# cc2650_48.net
KiCad netlist of a schematic drawn in EAGLE
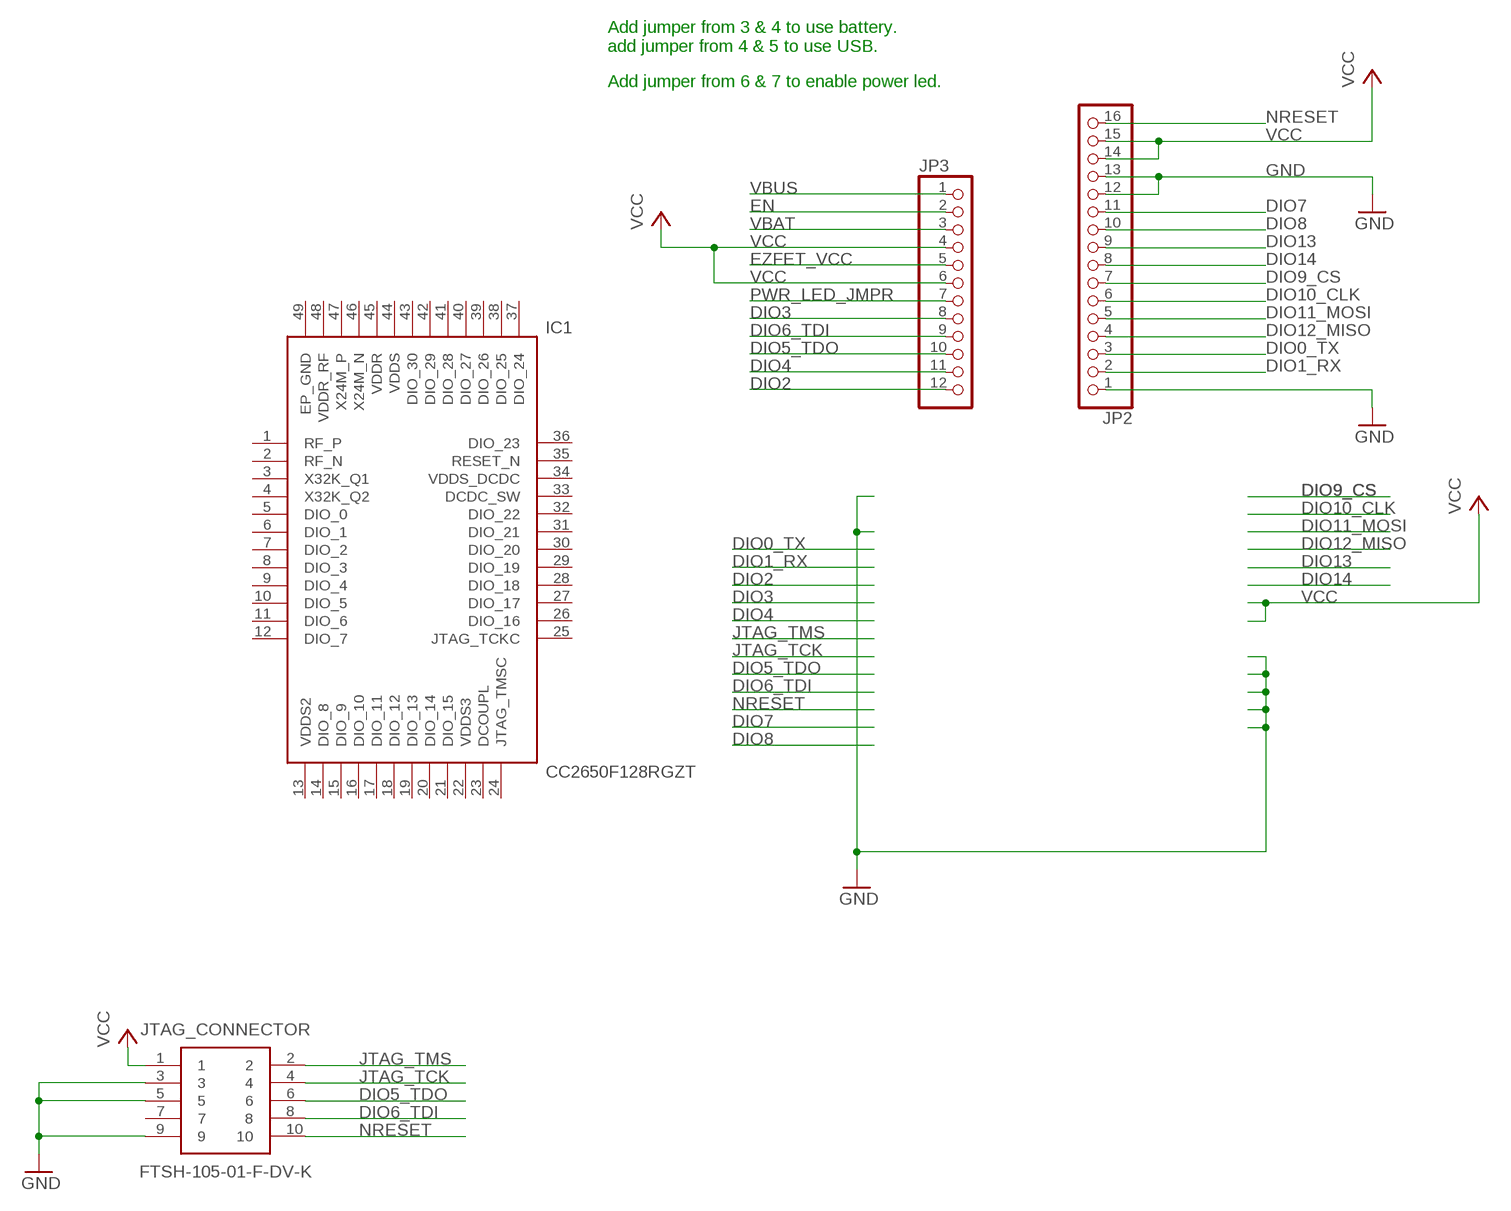
[diagram p0: schematic, sheet 1, part 1 of 2]
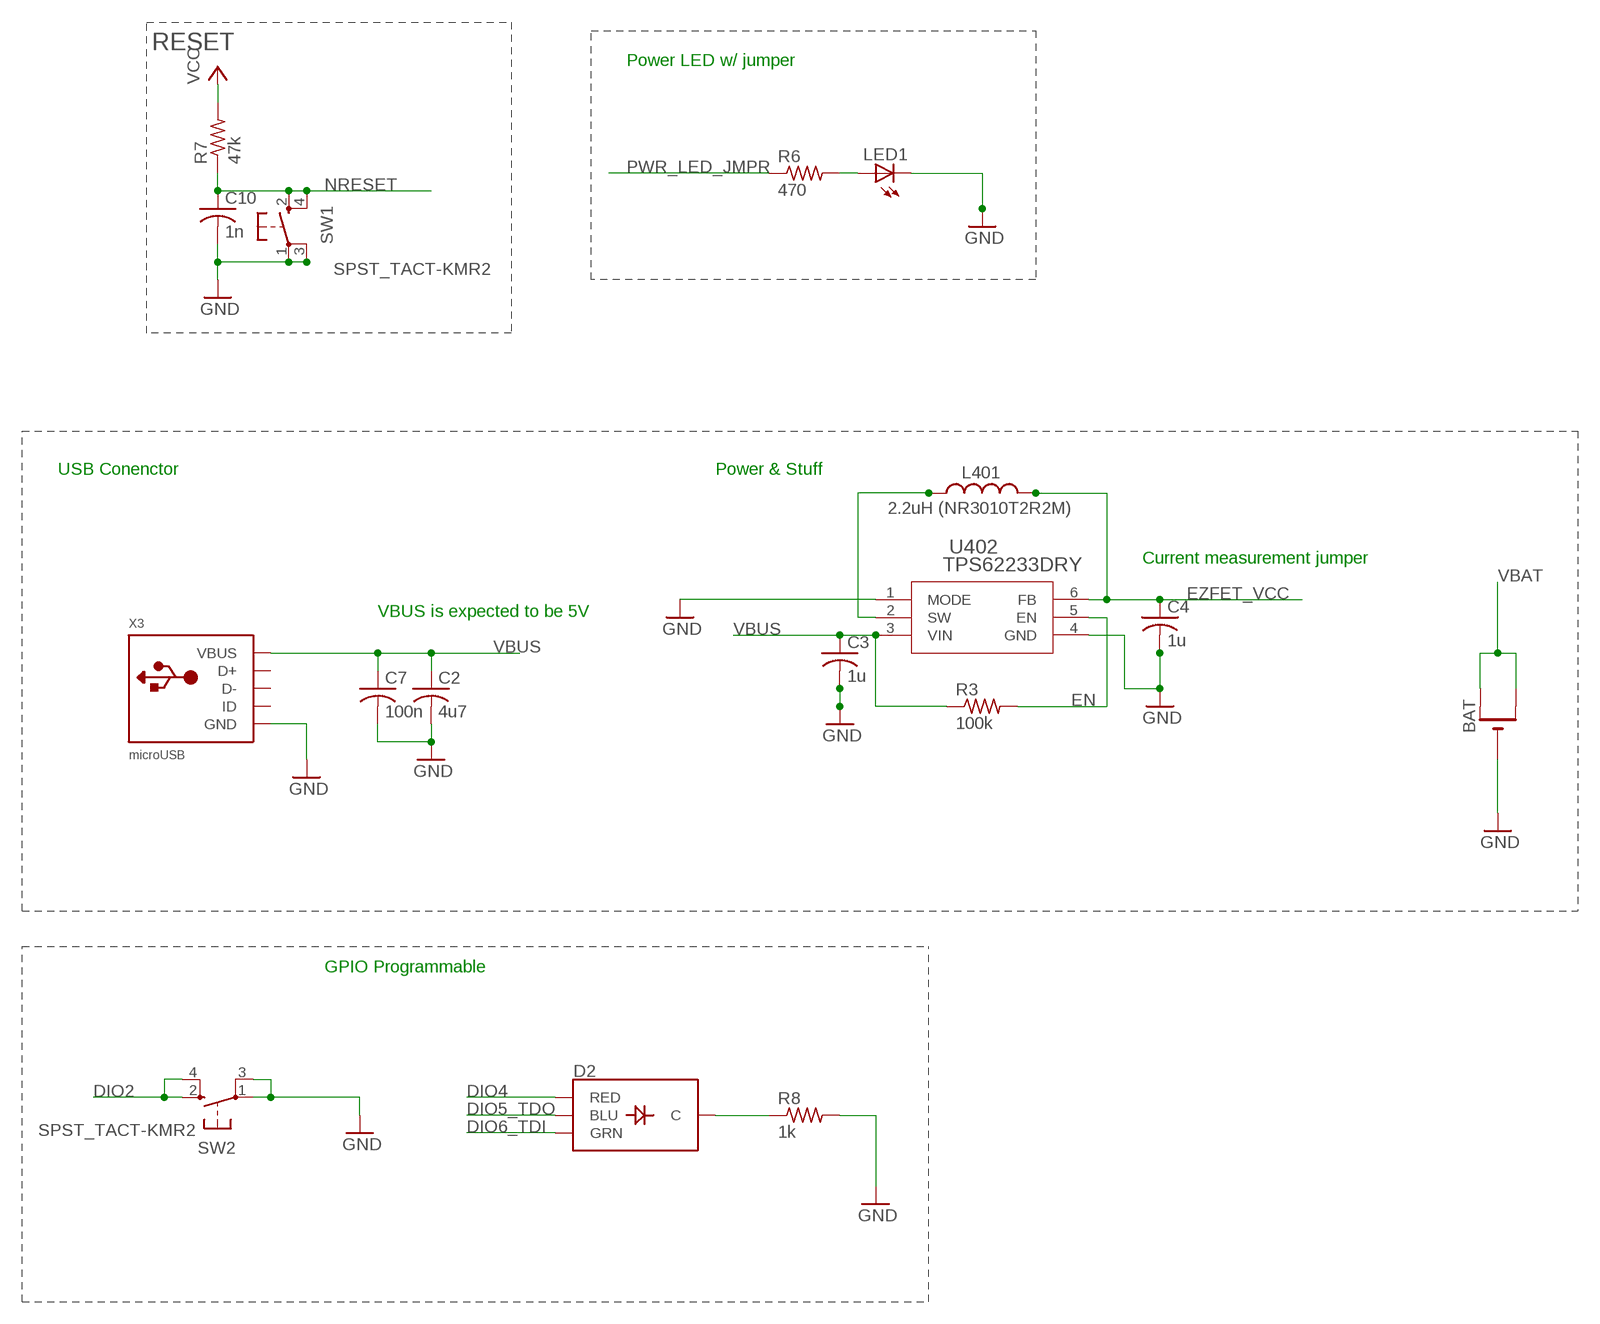
[diagram p1: schematic, sheet 1, part 2 of 2]

(export (version "E")
  (design (tool "Eeschema 10.0.6"))
  (components
    (comp (ref "BAT")
      (value "CR1220THM")
      (footprint "eagle-import:CR1220-THM")
      (fields (field (name "MF") "KEYSTONE ELECTR") (field (name "MPN") "3000"))
      (libsource (lib "eagle-import") (part "CR1220THM"))
    )
    (comp (ref "C2")
      (value "4u7")
      (footprint "eagle-import:C1206")
      (fields (field (name "MPN") "GRT31CC81E475KE01L"))
      (libsource (lib "eagle-import") (part "C-USC1206"))
    )
    (comp (ref "C3")
      (value "1u")
      (footprint "eagle-import:C0805")
      (fields (field (name "MPN") "C0805C105K5RACTU"))
      (libsource (lib "eagle-import") (part "C-USC0805"))
    )
    (comp (ref "C4")
      (value "1u")
      (footprint "eagle-import:C0805")
      (fields (field (name "MPN") "C0805C105K5RACTU"))
      (libsource (lib "eagle-import") (part "C-USC0805"))
    )
    (comp (ref "C7")
      (value "100n")
      (footprint "eagle-import:C0805")
      (libsource (lib "eagle-import") (part "C-USC0805"))
    )
    (comp (ref "C10")
      (value "1n")
      (footprint "eagle-import:C0805")
      (libsource (lib "eagle-import") (part "C-USC0805"))
    )
    (comp (ref "D2")
      (value "LED-RGB-CCPIRANHA")
      (footprint "eagle-import:LED_PIRANHA_5MM")
      (fields (field (name "MPN") "CLMVB-FKA-CFHEHLCBB7A363"))
      (libsource (lib "eagle-import") (part "LED-RGB-CCPIRANHA"))
    )
    (comp (ref "IC1")
      (value "CC2650F128RGZT")
      (footprint "eagle-import:QFN50P700X700X100-49N")
      (fields (field (name "RS_PART_NUMBER") "8751012P"))
      (libsource (lib "eagle-import") (part "CC2650F128RGZT"))
    )
    (comp (ref "JP2")
      (value "HEADER-1X16ROUND")
      (footprint "eagle-import:1X16_ROUND")
      (libsource (lib "eagle-import") (part "HEADER-1X16ROUND"))
    )
    (comp (ref "JP3")
      (value "HEADER-1X12")
      (footprint "eagle-import:1X12_ROUND")
      (libsource (lib "eagle-import") (part "HEADER-1X12"))
    )
    (comp (ref "JTAG_CONNECTOR")
      (value "FTSH-105-01-F-DV-K")
      (footprint "eagle-import:SAMTEC_FTSH-105-01-L-DV")
      (libsource (lib "eagle-import") (part "FTSH-105-01-F-DV-K"))
    )
    (comp (ref "L401")
      (value "2.2uH (NR3010T2R2M)")
      (footprint "eagle-import:L-NR3010")
      (fields (field (name "MPN") "NR3010T2R2M"))
      (libsource (lib "eagle-import") (part "L-NR3010"))
    )
    (comp (ref "LED1")
      (value "LEDCHIPLED_0805")
      (footprint "eagle-import:CHIPLED_0805")
      (libsource (lib "eagle-import") (part "LEDCHIPLED_0805"))
    )
    (comp (ref "R3")
      (value "100k")
      (footprint "eagle-import:R0805")
      (libsource (lib "eagle-import") (part "R-US_R0805"))
    )
    (comp (ref "R6")
      (value "470")
      (footprint "eagle-import:R0805")
      (libsource (lib "eagle-import") (part "R-US_R0805"))
    )
    (comp (ref "R7")
      (value "47k")
      (footprint "eagle-import:R0805")
      (libsource (lib "eagle-import") (part "R-US_R0805"))
    )
    (comp (ref "R8")
      (value "1k")
      (footprint "eagle-import:R0805")
      (libsource (lib "eagle-import") (part "R-US_R0805"))
    )
    (comp (ref "SW1")
      (value "SPST_TACT-KMR2")
      (footprint "eagle-import:KMR2")
      (libsource (lib "eagle-import") (part "SPST_TACT-KMR2"))
    )
    (comp (ref "SW2")
      (value "SPST_TACT-KMR2")
      (footprint "eagle-import:KMR2")
      (libsource (lib "eagle-import") (part "SPST_TACT-KMR2"))
    )
    (comp (ref "U402")
      (value "TPS62233DRY")
      (footprint "eagle-import:DRY6")
      (fields
        (field (name "GENERIC_PART_NUMBER") "TPS62231")
        (field (name "MANUFACTURER") "Texas Instruments")
        (field (name "MANUFACTURER_PART_NUMBER") "tps62231_dry_6")
      )
      (libsource (lib "eagle-import") (part "TPS6223X_DRY_6"))
    )
    (comp (ref "X3")
      (value "microUSB")
      (footprint "eagle-import:4UCONN_20329_V2")
      (libsource (lib "eagle-import") (part "USB_MICRO_20329_V2"))
    )
  )
  (nets
    (net (code "1") (name "/DIO0_TX") (class "Default")
      (node (ref "JP2") (pin "3") (pinfunction "3_3") (pintype "passive"))
    )
    (net (code "2") (name "/DIO1_RX") (class "Default")
      (node (ref "JP2") (pin "2") (pinfunction "2_2") (pintype "passive"))
    )
    (net (code "3") (name "/DIO2") (class "Default")
      (node (ref "JP3") (pin "12") (pinfunction "12_12") (pintype "passive"))
      (node (ref "SW2") (pin "2") (pinfunction "S_2") (pintype "passive"))
      (node (ref "SW2") (pin "4") (pinfunction "S1_4") (pintype "passive"))
    )
    (net (code "4") (name "/DIO3") (class "Default")
      (node (ref "JP3") (pin "8") (pinfunction "8_8") (pintype "passive"))
    )
    (net (code "5") (name "/DIO4") (class "Default")
      (node (ref "D2") (pin "R") (pinfunction "RED_R") (pintype "bidirectional"))
      (node (ref "JP3") (pin "11") (pinfunction "11_11") (pintype "passive"))
    )
    (net (code "6") (name "/DIO5_TDO") (class "Default")
      (node (ref "D2") (pin "B") (pinfunction "BLU_B") (pintype "bidirectional"))
      (node (ref "JP3") (pin "10") (pinfunction "10_10") (pintype "passive"))
      (node (ref "JTAG_CONNECTOR") (pin "6") (pinfunction "6_6") (pintype "passive"))
    )
    (net (code "7") (name "/DIO6_TDI") (class "Default")
      (node (ref "D2") (pin "G") (pinfunction "GRN_G") (pintype "bidirectional"))
      (node (ref "JP3") (pin "9") (pinfunction "9_9") (pintype "passive"))
      (node (ref "JTAG_CONNECTOR") (pin "8") (pinfunction "8_8") (pintype "passive"))
    )
    (net (code "8") (name "/DIO7") (class "Default")
      (node (ref "JP2") (pin "11") (pinfunction "11_11") (pintype "passive"))
    )
    (net (code "9") (name "/DIO8") (class "Default")
      (node (ref "JP2") (pin "10") (pinfunction "10_10") (pintype "passive"))
    )
    (net (code "10") (name "/DIO9_CS") (class "Default")
      (node (ref "JP2") (pin "7") (pinfunction "7_7") (pintype "passive"))
    )
    (net (code "11") (name "/DIO10_CLK") (class "Default")
      (node (ref "JP2") (pin "6") (pinfunction "6_6") (pintype "passive"))
    )
    (net (code "12") (name "/DIO11_MOSI") (class "Default")
      (node (ref "JP2") (pin "5") (pinfunction "5_5") (pintype "passive"))
    )
    (net (code "13") (name "/DIO12_MISO") (class "Default")
      (node (ref "JP2") (pin "4") (pinfunction "4_4") (pintype "passive"))
    )
    (net (code "14") (name "/DIO13") (class "Default")
      (node (ref "JP2") (pin "9") (pinfunction "9_9") (pintype "passive"))
    )
    (net (code "15") (name "/DIO14") (class "Default")
      (node (ref "JP2") (pin "8") (pinfunction "8_8") (pintype "passive"))
    )
    (net (code "16") (name "/EN") (class "Default")
      (node (ref "JP3") (pin "2") (pinfunction "2_2") (pintype "passive"))
      (node (ref "R3") (pin "2") (pinfunction "2_2") (pintype "passive"))
      (node (ref "U402") (pin "5") (pinfunction "EN_5") (pintype "input"))
    )
    (net (code "17") (name "/EP_GND") (class "Default")
      (node (ref "IC1") (pin "49") (pinfunction "EP_GND_49") (pintype "power_in"))
    )
    (net (code "18") (name "/EZFET_VCC") (class "Default")
      (node (ref "C4") (pin "1") (pinfunction "1_1") (pintype "passive"))
      (node (ref "JP3") (pin "5") (pinfunction "5_5") (pintype "passive"))
      (node (ref "L401") (pin "P$2") (pinfunction "2_P$2") (pintype "passive"))
      (node (ref "U402") (pin "6") (pinfunction "FB_6") (pintype "input"))
    )
    (net (code "19") (name "/JTAG_TCK") (class "Default")
      (node (ref "JTAG_CONNECTOR") (pin "4") (pinfunction "4_4") (pintype "passive"))
    )
    (net (code "20") (name "/JTAG_TMS") (class "Default")
      (node (ref "JTAG_CONNECTOR") (pin "2") (pinfunction "2_2") (pintype "passive"))
    )
    (net (code "21") (name "/NRESET") (class "Default")
      (node (ref "C10") (pin "1") (pinfunction "1_1") (pintype "passive"))
      (node (ref "JP2") (pin "16") (pinfunction "16_16") (pintype "passive"))
      (node (ref "JTAG_CONNECTOR") (pin "10") (pinfunction "10_10") (pintype "passive"))
      (node (ref "R7") (pin "1") (pinfunction "1_1") (pintype "passive"))
      (node (ref "SW1") (pin "2") (pinfunction "S_2") (pintype "passive"))
      (node (ref "SW1") (pin "4") (pinfunction "S1_4") (pintype "passive"))
    )
    (net (code "22") (name "/PWR_LED_JMPR") (class "Default")
      (node (ref "JP3") (pin "7") (pinfunction "7_7") (pintype "passive"))
      (node (ref "R6") (pin "1") (pinfunction "1_1") (pintype "passive"))
    )
    (net (code "23") (name "/VBAT") (class "Default")
      (node (ref "BAT") (pin "+1") (pinfunction "+_+1") (pintype "passive"))
      (node (ref "BAT") (pin "+2") (pinfunction "+1_+2") (pintype "passive"))
      (node (ref "JP3") (pin "3") (pinfunction "3_3") (pintype "passive"))
    )
    (net (code "24") (name "/VBUS") (class "Default")
      (node (ref "C2") (pin "1") (pinfunction "1_1") (pintype "passive"))
      (node (ref "C3") (pin "1") (pinfunction "1_1") (pintype "passive"))
      (node (ref "C7") (pin "1") (pinfunction "1_1") (pintype "passive"))
      (node (ref "JP3") (pin "1") (pinfunction "1_1") (pintype "passive"))
      (node (ref "R3") (pin "1") (pinfunction "1_1") (pintype "passive"))
      (node (ref "U402") (pin "3") (pinfunction "VIN_3") (pintype "power_in"))
      (node (ref "X3") (pin "VBUS") (pinfunction "VBUS_VBUS") (pintype "power_in"))
    )
    (net (code "25") (name "/VDDR") (class "Default")
      (node (ref "IC1") (pin "45") (pinfunction "VDDR_45") (pintype "power_in"))
    )
    (net (code "26") (name "/VDDR_RF") (class "Default")
      (node (ref "IC1") (pin "48") (pinfunction "VDDR_RF_48") (pintype "power_in"))
    )
    (net (code "27") (name "/VDDS") (class "Default")
      (node (ref "IC1") (pin "44") (pinfunction "VDDS_44") (pintype "power_in"))
    )
    (net (code "28") (name "/VDDS2") (class "Default")
      (node (ref "IC1") (pin "13") (pinfunction "VDDS2_13") (pintype "power_in"))
    )
    (net (code "29") (name "/VDDS3") (class "Default")
      (node (ref "IC1") (pin "22") (pinfunction "VDDS3_22") (pintype "power_in"))
    )
    (net (code "30") (name "/VDDS_DCDC") (class "Default")
      (node (ref "IC1") (pin "34") (pinfunction "VDDS_DCDC_34") (pintype "power_in"))
    )
    (net (code "31") (name "GND") (class "Default")
      (node (ref "BAT") (pin "-") (pinfunction "-_-") (pintype "passive"))
      (node (ref "C10") (pin "2") (pinfunction "2_2") (pintype "passive"))
      (node (ref "C2") (pin "2") (pinfunction "2_2") (pintype "passive"))
      (node (ref "C3") (pin "2") (pinfunction "2_2") (pintype "passive"))
      (node (ref "C4") (pin "2") (pinfunction "2_2") (pintype "passive"))
      (node (ref "C7") (pin "2") (pinfunction "2_2") (pintype "passive"))
      (node (ref "JP2") (pin "1") (pinfunction "1_1") (pintype "passive"))
      (node (ref "JP2") (pin "12") (pinfunction "12_12") (pintype "passive"))
      (node (ref "JP2") (pin "13") (pinfunction "13_13") (pintype "passive"))
      (node (ref "JTAG_CONNECTOR") (pin "3") (pinfunction "3_3") (pintype "passive"))
      (node (ref "JTAG_CONNECTOR") (pin "5") (pinfunction "5_5") (pintype "passive"))
      (node (ref "JTAG_CONNECTOR") (pin "9") (pinfunction "9_9") (pintype "passive"))
      (node (ref "LED1") (pin "C") (pinfunction "C_C") (pintype "passive"))
      (node (ref "R8") (pin "2") (pinfunction "2_2") (pintype "passive"))
      (node (ref "SW1") (pin "1") (pinfunction "P_1") (pintype "passive"))
      (node (ref "SW1") (pin "3") (pinfunction "P1_3") (pintype "passive"))
      (node (ref "SW2") (pin "1") (pinfunction "P_1") (pintype "passive"))
      (node (ref "SW2") (pin "3") (pinfunction "P1_3") (pintype "passive"))
      (node (ref "U402") (pin "1") (pinfunction "MODE_1") (pintype "input"))
      (node (ref "U402") (pin "4") (pinfunction "GND_4") (pintype "power_in"))
      (node (ref "X3") (pin "BASE@1") (pinfunction "GND_BASE@1") (pintype "power_in"))
      (node (ref "X3") (pin "BASE@2") (pinfunction "GND_BASE@2") (pintype "power_in"))
      (node (ref "X3") (pin "GND") (pinfunction "GND_GND") (pintype "power_in"))
      (node (ref "X3") (pin "SPRT@1") (pinfunction "GND_SPRT@1") (pintype "power_in"))
      (node (ref "X3") (pin "SPRT@2") (pinfunction "GND_SPRT@2") (pintype "power_in"))
      (node (ref "X3") (pin "SPRT@3") (pinfunction "GND_SPRT@3") (pintype "power_in"))
      (node (ref "X3") (pin "SPRT@4") (pinfunction "GND_SPRT@4") (pintype "power_in"))
    )
    (net (code "32") (name "Net-(D2-C)") (class "Default")
      (node (ref "D2") (pin "-") (pinfunction "C_-") (pintype "bidirectional"))
      (node (ref "R8") (pin "1") (pinfunction "1_1") (pintype "passive"))
    )
    (net (code "33") (name "Net-(L401-1)") (class "Default")
      (node (ref "L401") (pin "P$1") (pinfunction "1_P$1") (pintype "passive"))
      (node (ref "U402") (pin "2") (pinfunction "SW_2") (pintype "output"))
    )
    (net (code "34") (name "Net-(LED1-PadA)") (class "Default")
      (node (ref "LED1") (pin "A") (pinfunction "A_A") (pintype "passive"))
      (node (ref "R6") (pin "2") (pinfunction "2_2") (pintype "passive"))
    )
    (net (code "35") (name "VCC") (class "Default")
      (node (ref "JP2") (pin "14") (pinfunction "14_14") (pintype "passive"))
      (node (ref "JP2") (pin "15") (pinfunction "15_15") (pintype "passive"))
      (node (ref "JP3") (pin "4") (pinfunction "4_4") (pintype "passive"))
      (node (ref "JP3") (pin "6") (pinfunction "6_6") (pintype "passive"))
      (node (ref "JTAG_CONNECTOR") (pin "1") (pinfunction "1_1") (pintype "passive"))
      (node (ref "R7") (pin "2") (pinfunction "2_2") (pintype "passive"))
    )
    (net (code "36") (name "unconnected-(IC1-DCDC_SW-Pad33)") (class "Default")
      (node (ref "IC1") (pin "33") (pinfunction "DCDC_SW_33") (pintype "passive"))
    )
    (net (code "37") (name "unconnected-(IC1-DCOUPL-Pad23)") (class "Default")
      (node (ref "IC1") (pin "23") (pinfunction "DCOUPL_23") (pintype "passive"))
    )
    (net (code "38") (name "unconnected-(IC1-DIO_0-Pad5)") (class "Default")
      (node (ref "IC1") (pin "5") (pinfunction "DIO_0_5") (pintype "bidirectional"))
    )
    (net (code "39") (name "unconnected-(IC1-DIO_1-Pad6)") (class "Default")
      (node (ref "IC1") (pin "6") (pinfunction "DIO_1_6") (pintype "bidirectional"))
    )
    (net (code "40") (name "unconnected-(IC1-DIO_2-Pad7)") (class "Default")
      (node (ref "IC1") (pin "7") (pinfunction "DIO_2_7") (pintype "bidirectional"))
    )
    (net (code "41") (name "unconnected-(IC1-DIO_3-Pad8)") (class "Default")
      (node (ref "IC1") (pin "8") (pinfunction "DIO_3_8") (pintype "bidirectional"))
    )
    (net (code "42") (name "unconnected-(IC1-DIO_4-Pad9)") (class "Default")
      (node (ref "IC1") (pin "9") (pinfunction "DIO_4_9") (pintype "bidirectional"))
    )
    (net (code "43") (name "unconnected-(IC1-DIO_5-Pad10)") (class "Default")
      (node (ref "IC1") (pin "10") (pinfunction "DIO_5_10") (pintype "bidirectional"))
    )
    (net (code "44") (name "unconnected-(IC1-DIO_6-Pad11)") (class "Default")
      (node (ref "IC1") (pin "11") (pinfunction "DIO_6_11") (pintype "bidirectional"))
    )
    (net (code "45") (name "unconnected-(IC1-DIO_7-Pad12)") (class "Default")
      (node (ref "IC1") (pin "12") (pinfunction "DIO_7_12") (pintype "bidirectional"))
    )
    (net (code "46") (name "unconnected-(IC1-DIO_8-Pad14)") (class "Default")
      (node (ref "IC1") (pin "14") (pinfunction "DIO_8_14") (pintype "bidirectional"))
    )
    (net (code "47") (name "unconnected-(IC1-DIO_9-Pad15)") (class "Default")
      (node (ref "IC1") (pin "15") (pinfunction "DIO_9_15") (pintype "bidirectional"))
    )
    (net (code "48") (name "unconnected-(IC1-DIO_10-Pad16)") (class "Default")
      (node (ref "IC1") (pin "16") (pinfunction "DIO_10_16") (pintype "bidirectional"))
    )
    (net (code "49") (name "unconnected-(IC1-DIO_11-Pad17)") (class "Default")
      (node (ref "IC1") (pin "17") (pinfunction "DIO_11_17") (pintype "bidirectional"))
    )
    (net (code "50") (name "unconnected-(IC1-DIO_12-Pad18)") (class "Default")
      (node (ref "IC1") (pin "18") (pinfunction "DIO_12_18") (pintype "bidirectional"))
    )
    (net (code "51") (name "unconnected-(IC1-DIO_13-Pad19)") (class "Default")
      (node (ref "IC1") (pin "19") (pinfunction "DIO_13_19") (pintype "bidirectional"))
    )
    (net (code "52") (name "unconnected-(IC1-DIO_14-Pad20)") (class "Default")
      (node (ref "IC1") (pin "20") (pinfunction "DIO_14_20") (pintype "bidirectional"))
    )
    (net (code "53") (name "unconnected-(IC1-DIO_15-Pad21)") (class "Default")
      (node (ref "IC1") (pin "21") (pinfunction "DIO_15_21") (pintype "bidirectional"))
    )
    (net (code "54") (name "unconnected-(IC1-DIO_16-Pad26)") (class "Default")
      (node (ref "IC1") (pin "26") (pinfunction "DIO_16_26") (pintype "bidirectional"))
    )
    (net (code "55") (name "unconnected-(IC1-DIO_17-Pad27)") (class "Default")
      (node (ref "IC1") (pin "27") (pinfunction "DIO_17_27") (pintype "bidirectional"))
    )
    (net (code "56") (name "unconnected-(IC1-DIO_18-Pad28)") (class "Default")
      (node (ref "IC1") (pin "28") (pinfunction "DIO_18_28") (pintype "bidirectional"))
    )
    (net (code "57") (name "unconnected-(IC1-DIO_19-Pad29)") (class "Default")
      (node (ref "IC1") (pin "29") (pinfunction "DIO_19_29") (pintype "bidirectional"))
    )
    (net (code "58") (name "unconnected-(IC1-DIO_20-Pad30)") (class "Default")
      (node (ref "IC1") (pin "30") (pinfunction "DIO_20_30") (pintype "bidirectional"))
    )
    (net (code "59") (name "unconnected-(IC1-DIO_21-Pad31)") (class "Default")
      (node (ref "IC1") (pin "31") (pinfunction "DIO_21_31") (pintype "bidirectional"))
    )
    (net (code "60") (name "unconnected-(IC1-DIO_22-Pad32)") (class "Default")
      (node (ref "IC1") (pin "32") (pinfunction "DIO_22_32") (pintype "bidirectional"))
    )
    (net (code "61") (name "unconnected-(IC1-DIO_23-Pad36)") (class "Default")
      (node (ref "IC1") (pin "36") (pinfunction "DIO_23_36") (pintype "bidirectional"))
    )
    (net (code "62") (name "unconnected-(IC1-DIO_24-Pad37)") (class "Default")
      (node (ref "IC1") (pin "37") (pinfunction "DIO_24_37") (pintype "bidirectional"))
    )
    (net (code "63") (name "unconnected-(IC1-DIO_25-Pad38)") (class "Default")
      (node (ref "IC1") (pin "38") (pinfunction "DIO_25_38") (pintype "bidirectional"))
    )
    (net (code "64") (name "unconnected-(IC1-DIO_26-Pad39)") (class "Default")
      (node (ref "IC1") (pin "39") (pinfunction "DIO_26_39") (pintype "bidirectional"))
    )
    (net (code "65") (name "unconnected-(IC1-DIO_27-Pad40)") (class "Default")
      (node (ref "IC1") (pin "40") (pinfunction "DIO_27_40") (pintype "bidirectional"))
    )
    (net (code "66") (name "unconnected-(IC1-DIO_28-Pad41)") (class "Default")
      (node (ref "IC1") (pin "41") (pinfunction "DIO_28_41") (pintype "bidirectional"))
    )
    (net (code "67") (name "unconnected-(IC1-DIO_29-Pad42)") (class "Default")
      (node (ref "IC1") (pin "42") (pinfunction "DIO_29_42") (pintype "bidirectional"))
    )
    (net (code "68") (name "unconnected-(IC1-DIO_30-Pad43)") (class "Default")
      (node (ref "IC1") (pin "43") (pinfunction "DIO_30_43") (pintype "bidirectional"))
    )
    (net (code "69") (name "unconnected-(IC1-JTAG_TCKC-Pad25)") (class "Default")
      (node (ref "IC1") (pin "25") (pinfunction "JTAG_TCKC_25") (pintype "passive"))
    )
    (net (code "70") (name "unconnected-(IC1-JTAG_TMSC-Pad24)") (class "Default")
      (node (ref "IC1") (pin "24") (pinfunction "JTAG_TMSC_24") (pintype "passive"))
    )
    (net (code "71") (name "unconnected-(IC1-RESET_N-Pad35)") (class "Default")
      (node (ref "IC1") (pin "35") (pinfunction "RESET_N_35") (pintype "passive"))
    )
    (net (code "72") (name "unconnected-(IC1-RF_N-Pad2)") (class "Default")
      (node (ref "IC1") (pin "2") (pinfunction "RF_N_2") (pintype "passive"))
    )
    (net (code "73") (name "unconnected-(IC1-RF_P-Pad1)") (class "Default")
      (node (ref "IC1") (pin "1") (pinfunction "RF_P_1") (pintype "passive"))
    )
    (net (code "74") (name "unconnected-(IC1-X24M_N-Pad46)") (class "Default")
      (node (ref "IC1") (pin "46") (pinfunction "X24M_N_46") (pintype "passive"))
    )
    (net (code "75") (name "unconnected-(IC1-X24M_P-Pad47)") (class "Default")
      (node (ref "IC1") (pin "47") (pinfunction "X24M_P_47") (pintype "passive"))
    )
    (net (code "76") (name "unconnected-(IC1-X32K_Q1-Pad3)") (class "Default")
      (node (ref "IC1") (pin "3") (pinfunction "X32K_Q1_3") (pintype "passive"))
    )
    (net (code "77") (name "unconnected-(IC1-X32K_Q2-Pad4)") (class "Default")
      (node (ref "IC1") (pin "4") (pinfunction "X32K_Q2_4") (pintype "passive"))
    )
    (net (code "78") (name "unconnected-(JTAG_CONNECTOR-Pad7)") (class "Default")
      (node (ref "JTAG_CONNECTOR") (pin "7") (pinfunction "7_7") (pintype "passive"))
    )
    (net (code "79") (name "unconnected-(X3-PadD+)") (class "Default")
      (node (ref "X3") (pin "D+") (pinfunction "D+_D+") (pintype "bidirectional"))
    )
    (net (code "80") (name "unconnected-(X3-PadD-)") (class "Default")
      (node (ref "X3") (pin "D-") (pinfunction "D-_D-") (pintype "bidirectional"))
    )
    (net (code "81") (name "unconnected-(X3-PadID)") (class "Default")
      (node (ref "X3") (pin "ID") (pinfunction "ID_ID") (pintype "bidirectional"))
    )
  )
)
